# VisualightMicroBulb_03.net
KiCad netlist of a schematic drawn in EAGLE
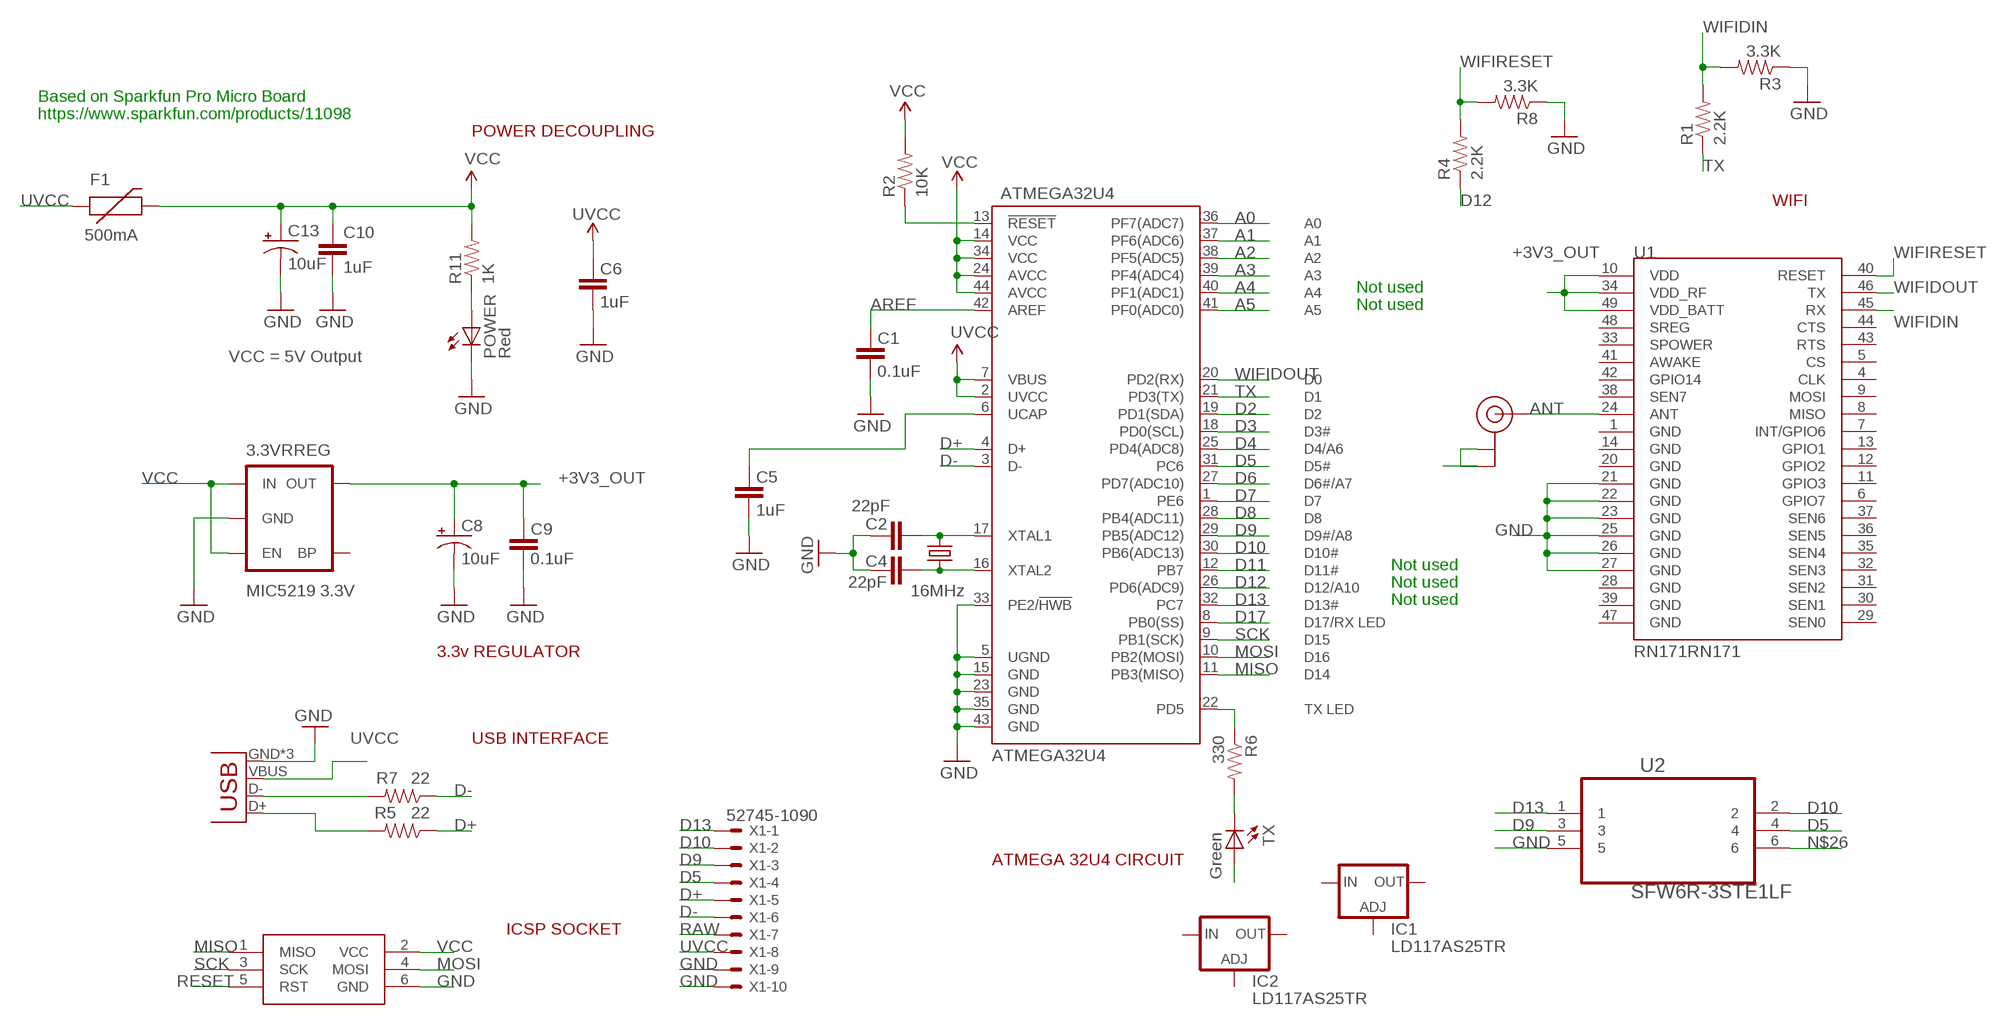
[diagram p0: schematic, sheet 1]

(export (version "E")
  (design (tool "Eeschema 10.0.6"))
  (components
    (comp (ref "3.3VRREG")
      (value "MIC5219 3.3V")
      (footprint "eagle-import:SOT23-5")
      (libsource (lib "eagle-import") (part "V_REG_MIC52193.3V"))
    )
    (comp (ref "ATMEGA32U4")
      (value "ATMEGA32U4")
      (footprint "eagle-import:SPARKFUN-DIGITALIC_TQFP44")
      (libsource (lib "eagle-import") (part "ATMEGA32U4TQFP"))
    )
    (comp (ref "C1")
      (value "0.1uF")
      (footprint "eagle-import:0402-CAP")
      (libsource (lib "eagle-import") (part "CAP0402-CAP"))
    )
    (comp (ref "C2")
      (value "22pF")
      (footprint "eagle-import:0402-CAP")
      (libsource (lib "eagle-import") (part "CAP0402-CAP"))
    )
    (comp (ref "C4")
      (value "22pF")
      (footprint "eagle-import:0402-CAP")
      (libsource (lib "eagle-import") (part "CAP0402-CAP"))
    )
    (comp (ref "C5")
      (value "1uF")
      (footprint "eagle-import:0402-CAP")
      (libsource (lib "eagle-import") (part "CAP0402-CAP"))
    )
    (comp (ref "C6")
      (value "1uF")
      (footprint "eagle-import:0402-CAP")
      (libsource (lib "eagle-import") (part "CAP0402-CAP"))
    )
    (comp (ref "C8")
      (value "10uF")
      (footprint "eagle-import:EIA3216")
      (libsource (lib "eagle-import") (part "CAP_POL1206"))
    )
    (comp (ref "C9")
      (value "0.1uF")
      (footprint "eagle-import:0402-CAP")
      (libsource (lib "eagle-import") (part "CAP0402-CAP"))
    )
    (comp (ref "C10")
      (value "1uF")
      (footprint "eagle-import:0402-CAP")
      (libsource (lib "eagle-import") (part "CAP0402-CAP"))
    )
    (comp (ref "C13")
      (value "10uF")
      (footprint "eagle-import:EIA3216")
      (libsource (lib "eagle-import") (part "CAP_POL1206"))
    )
    (comp (ref "F1")
      (value "500mA")
      (footprint "eagle-import:PTC-1206")
      (libsource (lib "eagle-import") (part "PTCSMD"))
    )
    (comp (ref "IC1")
      (value "LD117AS25TR")
      (footprint "eagle-import:SOT223")
      (libsource (lib "eagle-import") (part "LD117A?S25TR"))
    )
    (comp (ref "IC2")
      (value "LD117AS25TR")
      (footprint "eagle-import:SOT223")
      (libsource (lib "eagle-import") (part "LD117A?S25TR"))
    )
    (comp (ref "ISP1")
      (value "AVRISP-6")
      (footprint "eagle-import:AVRISP")
      (libsource (lib "eagle-import") (part "AVRISP-6"))
    )
    (comp (ref "POWER")
      (value "Red")
      (footprint "eagle-import:LED-0603")
      (libsource (lib "eagle-import") (part "LED0603"))
    )
    (comp (ref "R1")
      (value "2.2K")
      (footprint "eagle-import:0402-RES")
      (libsource (lib "eagle-import") (part "RESISTOR0402-RES"))
    )
    (comp (ref "R2")
      (value "10K")
      (footprint "eagle-import:0402-RES")
      (libsource (lib "eagle-import") (part "RESISTOR0402-RES"))
    )
    (comp (ref "R3")
      (value "3.3K")
      (footprint "eagle-import:0402-RES")
      (libsource (lib "eagle-import") (part "RESISTOR0402-RES"))
    )
    (comp (ref "R4")
      (value "2.2K")
      (footprint "eagle-import:0402-RES")
      (libsource (lib "eagle-import") (part "RESISTOR0402-RES"))
    )
    (comp (ref "R5")
      (value "22")
      (footprint "eagle-import:0402-RES")
      (libsource (lib "eagle-import") (part "RESISTOR0402-RES"))
    )
    (comp (ref "R6")
      (value "330")
      (footprint "eagle-import:0402-RES")
      (libsource (lib "eagle-import") (part "RESISTOR0402-RES"))
    )
    (comp (ref "R7")
      (value "22")
      (footprint "eagle-import:0402-RES")
      (libsource (lib "eagle-import") (part "RESISTOR0402-RES"))
    )
    (comp (ref "R8")
      (value "3.3K")
      (footprint "eagle-import:0402-RES")
      (libsource (lib "eagle-import") (part "RESISTOR0402-RES"))
    )
    (comp (ref "R11")
      (value "1K")
      (footprint "eagle-import:0402-RES")
      (libsource (lib "eagle-import") (part "RESISTOR0402-RES"))
    )
    (comp (ref "TX")
      (value "Green")
      (footprint "eagle-import:LED-0603")
      (libsource (lib "eagle-import") (part "LED0603"))
    )
    (comp (ref "U$1")
      (value "U.FL")
      (footprint "eagle-import:U.FL")
      (libsource (lib "eagle-import") (part "U.FL"))
    )
    (comp (ref "U1")
      (value "RN171RN171")
      (footprint "eagle-import:RN171")
      (libsource (lib "eagle-import") (part "RN171RN171"))
    )
    (comp (ref "U2")
      (value "SFW6R-3STE1LF")
      (footprint "eagle-import:FCI_SFW6R-3STE1LF")
      (libsource (lib "eagle-import") (part "SFW6R-3STE1LF"))
    )
    (comp (ref "X1")
      (value "52745-1090")
      (footprint "eagle-import:52745-1090")
      (libsource (lib "eagle-import") (part "52745-1090"))
    )
    (comp (ref "X2")
      (value "USB-MICROB")
      (footprint "eagle-import:USB-MICROB")
      (libsource (lib "eagle-import") (part "USB-MICROB"))
    )
    (comp (ref "Y1")
      (value "16MHz")
      (footprint "eagle-import:CRYSTAL-SMD-5X3")
      (libsource (lib "eagle-import") (part "CRYSTAL5X3"))
    )
  )
  (nets
    (net (code "1") (name "/+3V3_OUT") (class "Default")
      (node (ref "3.3VRREG") (pin "5") (pinfunction "OUT_5") (pintype "passive"))
      (node (ref "C8") (pin "A") (pinfunction "+_A") (pintype "passive"))
      (node (ref "C9") (pin "2") (pinfunction "2_2") (pintype "passive"))
      (node (ref "U1") (pin "10") (pinfunction "VDD_10") (pintype "bidirectional"))
      (node (ref "U1") (pin "34") (pinfunction "VDD_RF_34") (pintype "bidirectional"))
      (node (ref "U1") (pin "49") (pinfunction "VDD_BATT_49") (pintype "bidirectional"))
    )
    (net (code "2") (name "/A0") (class "Default")
      (node (ref "ATMEGA32U4") (pin "36") (pinfunction "PF7(ADC7)_36") (pintype "bidirectional"))
    )
    (net (code "3") (name "/A1") (class "Default")
      (node (ref "ATMEGA32U4") (pin "37") (pinfunction "PF6(ADC6)_37") (pintype "bidirectional"))
    )
    (net (code "4") (name "/A2") (class "Default")
      (node (ref "ATMEGA32U4") (pin "38") (pinfunction "PF5(ADC5)_38") (pintype "bidirectional"))
    )
    (net (code "5") (name "/A3") (class "Default")
      (node (ref "ATMEGA32U4") (pin "39") (pinfunction "PF4(ADC4)_39") (pintype "bidirectional"))
    )
    (net (code "6") (name "/A4") (class "Default")
      (node (ref "ATMEGA32U4") (pin "40") (pinfunction "PF1(ADC1)_40") (pintype "bidirectional"))
    )
    (net (code "7") (name "/A5") (class "Default")
      (node (ref "ATMEGA32U4") (pin "41") (pinfunction "PF0(ADC0)_41") (pintype "bidirectional"))
    )
    (net (code "8") (name "/ANT") (class "Default")
      (node (ref "U$1") (pin "P$3") (pinfunction "SIGNAL_P$3") (pintype "bidirectional"))
      (node (ref "U1") (pin "24") (pinfunction "ANT_24") (pintype "bidirectional"))
    )
    (net (code "9") (name "/AREF") (class "Default")
      (node (ref "ATMEGA32U4") (pin "42") (pinfunction "AREF_42") (pintype "bidirectional"))
      (node (ref "C1") (pin "2") (pinfunction "2_2") (pintype "passive"))
    )
    (net (code "10") (name "/D+") (class "Default")
      (node (ref "ATMEGA32U4") (pin "4") (pinfunction "D+_4") (pintype "bidirectional"))
      (node (ref "R5") (pin "1") (pinfunction "1_1") (pintype "passive"))
      (node (ref "X1") (pin "5") (pinfunction "S_5") (pintype "passive"))
    )
    (net (code "11") (name "/D-") (class "Default")
      (node (ref "ATMEGA32U4") (pin "3") (pinfunction "D-_3") (pintype "bidirectional"))
      (node (ref "R7") (pin "1") (pinfunction "1_1") (pintype "passive"))
      (node (ref "X1") (pin "6") (pinfunction "S_6") (pintype "passive"))
    )
    (net (code "12") (name "/D2") (class "Default")
      (node (ref "ATMEGA32U4") (pin "19") (pinfunction "PD1(SDA)_19") (pintype "bidirectional"))
    )
    (net (code "13") (name "/D3") (class "Default")
      (node (ref "ATMEGA32U4") (pin "18") (pinfunction "PD0(SCL)_18") (pintype "bidirectional"))
    )
    (net (code "14") (name "/D4") (class "Default")
      (node (ref "ATMEGA32U4") (pin "25") (pinfunction "PD4(ADC8)_25") (pintype "bidirectional"))
    )
    (net (code "15") (name "/D5") (class "Default")
      (node (ref "ATMEGA32U4") (pin "31") (pinfunction "PC6_31") (pintype "bidirectional"))
      (node (ref "U2") (pin "4") (pinfunction "4_4") (pintype "passive"))
      (node (ref "X1") (pin "4") (pinfunction "S_4") (pintype "passive"))
    )
    (net (code "16") (name "/D6") (class "Default")
      (node (ref "ATMEGA32U4") (pin "27") (pinfunction "PD7(ADC10)_27") (pintype "bidirectional"))
    )
    (net (code "17") (name "/D7") (class "Default")
      (node (ref "ATMEGA32U4") (pin "1") (pinfunction "PE6_1") (pintype "bidirectional"))
    )
    (net (code "18") (name "/D8") (class "Default")
      (node (ref "ATMEGA32U4") (pin "28") (pinfunction "PB4(ADC11)_28") (pintype "bidirectional"))
    )
    (net (code "19") (name "/D9") (class "Default")
      (node (ref "ATMEGA32U4") (pin "29") (pinfunction "PB5(ADC12)_29") (pintype "bidirectional"))
      (node (ref "U2") (pin "3") (pinfunction "3_3") (pintype "passive"))
      (node (ref "X1") (pin "3") (pinfunction "S_3") (pintype "passive"))
    )
    (net (code "20") (name "/D10") (class "Default")
      (node (ref "ATMEGA32U4") (pin "30") (pinfunction "PB6(ADC13)_30") (pintype "bidirectional"))
      (node (ref "U2") (pin "2") (pinfunction "2_2") (pintype "passive"))
      (node (ref "X1") (pin "2") (pinfunction "S_2") (pintype "passive"))
    )
    (net (code "21") (name "/D11") (class "Default")
      (node (ref "ATMEGA32U4") (pin "12") (pinfunction "PB7_12") (pintype "bidirectional"))
    )
    (net (code "22") (name "/D12") (class "Default")
      (node (ref "ATMEGA32U4") (pin "26") (pinfunction "PD6(ADC9)_26") (pintype "bidirectional"))
      (node (ref "R4") (pin "1") (pinfunction "1_1") (pintype "passive"))
    )
    (net (code "23") (name "/D13") (class "Default")
      (node (ref "ATMEGA32U4") (pin "32") (pinfunction "PC7_32") (pintype "bidirectional"))
      (node (ref "U2") (pin "1") (pinfunction "1_1") (pintype "passive"))
      (node (ref "X1") (pin "1") (pinfunction "S_1") (pintype "passive"))
    )
    (net (code "24") (name "/D17") (class "Default")
      (node (ref "ATMEGA32U4") (pin "8") (pinfunction "PB0(SS)_8") (pintype "bidirectional"))
    )
    (net (code "25") (name "/MISO") (class "Default")
      (node (ref "ATMEGA32U4") (pin "11") (pinfunction "PB3(MISO)_11") (pintype "bidirectional"))
      (node (ref "ISP1") (pin "1") (pinfunction "MISO_1") (pintype "input"))
    )
    (net (code "26") (name "/MOSI") (class "Default")
      (node (ref "ATMEGA32U4") (pin "10") (pinfunction "PB2(MOSI)_10") (pintype "bidirectional"))
      (node (ref "ISP1") (pin "4") (pinfunction "MOSI_4") (pintype "output"))
    )
    (net (code "27") (name "/N$26") (class "Default")
      (node (ref "U2") (pin "6") (pinfunction "6_6") (pintype "passive"))
    )
    (net (code "28") (name "/RAW") (class "Default")
      (node (ref "X1") (pin "7") (pinfunction "S_7") (pintype "passive"))
    )
    (net (code "29") (name "/RESET") (class "Default")
      (node (ref "ATMEGA32U4") (pin "13") (pinfunction "~{RESET}_13") (pintype "bidirectional"))
      (node (ref "ISP1") (pin "5") (pinfunction "RST_5") (pintype "output"))
      (node (ref "R2") (pin "1") (pinfunction "1_1") (pintype "passive"))
    )
    (net (code "30") (name "/SCK") (class "Default")
      (node (ref "ATMEGA32U4") (pin "9") (pinfunction "PB1(SCK)_9") (pintype "bidirectional"))
      (node (ref "ISP1") (pin "3") (pinfunction "SCK_3") (pintype "output"))
    )
    (net (code "31") (name "/TX") (class "Default")
      (node (ref "ATMEGA32U4") (pin "21") (pinfunction "PD3(TX)_21") (pintype "bidirectional"))
      (node (ref "R1") (pin "1") (pinfunction "1_1") (pintype "passive"))
    )
    (net (code "32") (name "/WIFIDIN") (class "Default")
      (node (ref "R1") (pin "2") (pinfunction "2_2") (pintype "passive"))
      (node (ref "R3") (pin "2") (pinfunction "2_2") (pintype "passive"))
      (node (ref "U1") (pin "45") (pinfunction "RX_45") (pintype "bidirectional"))
    )
    (net (code "33") (name "/WIFIDOUT") (class "Default")
      (node (ref "ATMEGA32U4") (pin "20") (pinfunction "PD2(RX)_20") (pintype "bidirectional"))
      (node (ref "U1") (pin "46") (pinfunction "TX_46") (pintype "bidirectional"))
    )
    (net (code "34") (name "/WIFIRESET") (class "Default")
      (node (ref "R4") (pin "2") (pinfunction "2_2") (pintype "passive"))
      (node (ref "R8") (pin "2") (pinfunction "2_2") (pintype "passive"))
      (node (ref "U1") (pin "40") (pinfunction "RESET_40") (pintype "bidirectional"))
    )
    (net (code "35") (name "GND") (class "Default")
      (node (ref "3.3VRREG") (pin "2") (pinfunction "GND_2") (pintype "input"))
      (node (ref "ATMEGA32U4") (pin "15") (pinfunction "GND_15") (pintype "bidirectional"))
      (node (ref "ATMEGA32U4") (pin "23") (pinfunction "GND_23") (pintype "bidirectional"))
      (node (ref "ATMEGA32U4") (pin "33") (pinfunction "PE2/~{HWB}_33") (pintype "bidirectional"))
      (node (ref "ATMEGA32U4") (pin "35") (pinfunction "GND_35") (pintype "bidirectional"))
      (node (ref "ATMEGA32U4") (pin "43") (pinfunction "GND_43") (pintype "bidirectional"))
      (node (ref "ATMEGA32U4") (pin "5") (pinfunction "UGND_5") (pintype "bidirectional"))
      (node (ref "C1") (pin "1") (pinfunction "1_1") (pintype "passive"))
      (node (ref "C10") (pin "2") (pinfunction "2_2") (pintype "passive"))
      (node (ref "C13") (pin "C") (pinfunction "-_C") (pintype "passive"))
      (node (ref "C2") (pin "2") (pinfunction "2_2") (pintype "passive"))
      (node (ref "C4") (pin "2") (pinfunction "2_2") (pintype "passive"))
      (node (ref "C5") (pin "1") (pinfunction "1_1") (pintype "passive"))
      (node (ref "C6") (pin "1") (pinfunction "1_1") (pintype "passive"))
      (node (ref "C8") (pin "C") (pinfunction "-_C") (pintype "passive"))
      (node (ref "C9") (pin "1") (pinfunction "1_1") (pintype "passive"))
      (node (ref "ISP1") (pin "6") (pinfunction "GND_6") (pintype "power_in"))
      (node (ref "POWER") (pin "C") (pinfunction "C_C") (pintype "passive"))
      (node (ref "R3") (pin "1") (pinfunction "1_1") (pintype "passive"))
      (node (ref "R8") (pin "1") (pinfunction "1_1") (pintype "passive"))
      (node (ref "U$1") (pin "P$1") (pinfunction "GND_P$1") (pintype "bidirectional"))
      (node (ref "U$1") (pin "P$2") (pinfunction "GND_P$2") (pintype "bidirectional"))
      (node (ref "U1") (pin "21") (pinfunction "GND_21") (pintype "bidirectional"))
      (node (ref "U1") (pin "22") (pinfunction "GND_22") (pintype "bidirectional"))
      (node (ref "U1") (pin "23") (pinfunction "GND_23") (pintype "bidirectional"))
      (node (ref "U1") (pin "25") (pinfunction "GND_25") (pintype "bidirectional"))
      (node (ref "U1") (pin "26") (pinfunction "GND_26") (pintype "bidirectional"))
      (node (ref "U1") (pin "27") (pinfunction "GND_27") (pintype "bidirectional"))
      (node (ref "U2") (pin "5") (pinfunction "5_5") (pintype "passive"))
      (node (ref "X1") (pin "10") (pinfunction "S_10") (pintype "passive"))
      (node (ref "X1") (pin "9") (pinfunction "S_9") (pintype "passive"))
      (node (ref "X2") (pin "GND") (pinfunction "GND_GND") (pintype "bidirectional"))
      (node (ref "X2") (pin "MT1") (pinfunction "GND_MT1") (pintype "bidirectional"))
      (node (ref "X2") (pin "MT2") (pinfunction "GND_MT2") (pintype "bidirectional"))
    )
    (net (code "36") (name "Net-(ATMEGA32U4-PD5)") (class "Default")
      (node (ref "ATMEGA32U4") (pin "22") (pinfunction "PD5_22") (pintype "bidirectional"))
      (node (ref "R6") (pin "1") (pinfunction "1_1") (pintype "passive"))
    )
    (net (code "37") (name "Net-(ATMEGA32U4-UCAP)") (class "Default")
      (node (ref "ATMEGA32U4") (pin "6") (pinfunction "UCAP_6") (pintype "bidirectional"))
      (node (ref "C5") (pin "2") (pinfunction "2_2") (pintype "passive"))
    )
    (net (code "38") (name "Net-(ATMEGA32U4-XTAL1)") (class "Default")
      (node (ref "ATMEGA32U4") (pin "17") (pinfunction "XTAL1_17") (pintype "bidirectional"))
      (node (ref "C2") (pin "1") (pinfunction "1_1") (pintype "passive"))
      (node (ref "Y1") (pin "3") (pinfunction "2_3") (pintype "passive"))
    )
    (net (code "39") (name "Net-(ATMEGA32U4-XTAL2)") (class "Default")
      (node (ref "ATMEGA32U4") (pin "16") (pinfunction "XTAL2_16") (pintype "bidirectional"))
      (node (ref "C4") (pin "1") (pinfunction "1_1") (pintype "passive"))
      (node (ref "Y1") (pin "1") (pinfunction "1_1") (pintype "passive"))
    )
    (net (code "40") (name "Net-(POWER-PadA)") (class "Default")
      (node (ref "POWER") (pin "A") (pinfunction "A_A") (pintype "passive"))
      (node (ref "R11") (pin "1") (pinfunction "1_1") (pintype "passive"))
    )
    (net (code "41") (name "Net-(R5-Pad2)") (class "Default")
      (node (ref "R5") (pin "2") (pinfunction "2_2") (pintype "passive"))
      (node (ref "X2") (pin "D+") (pinfunction "D+_D+") (pintype "bidirectional"))
    )
    (net (code "42") (name "Net-(R6-Pad2)") (class "Default")
      (node (ref "R6") (pin "2") (pinfunction "2_2") (pintype "passive"))
      (node (ref "TX") (pin "C") (pinfunction "C_C") (pintype "passive"))
    )
    (net (code "43") (name "Net-(R7-Pad2)") (class "Default")
      (node (ref "R7") (pin "2") (pinfunction "2_2") (pintype "passive"))
      (node (ref "X2") (pin "D-") (pinfunction "D-_D-") (pintype "bidirectional"))
    )
    (net (code "44") (name "UVCC") (class "Default")
      (node (ref "ATMEGA32U4") (pin "2") (pinfunction "UVCC_2") (pintype "bidirectional"))
      (node (ref "ATMEGA32U4") (pin "7") (pinfunction "VBUS_7") (pintype "bidirectional"))
      (node (ref "C6") (pin "2") (pinfunction "2_2") (pintype "passive"))
      (node (ref "F1") (pin "1") (pinfunction "1_1") (pintype "bidirectional"))
      (node (ref "X1") (pin "8") (pinfunction "S_8") (pintype "passive"))
      (node (ref "X2") (pin "VBUS") (pinfunction "VBUS_VBUS") (pintype "bidirectional"))
    )
    (net (code "45") (name "VCC") (class "Default")
      (node (ref "3.3VRREG") (pin "1") (pinfunction "IN_1") (pintype "input"))
      (node (ref "3.3VRREG") (pin "3") (pinfunction "EN_3") (pintype "input"))
      (node (ref "ATMEGA32U4") (pin "14") (pinfunction "VCC_14") (pintype "bidirectional"))
      (node (ref "ATMEGA32U4") (pin "24") (pinfunction "AVCC_24") (pintype "bidirectional"))
      (node (ref "ATMEGA32U4") (pin "34") (pinfunction "VCC_34") (pintype "bidirectional"))
      (node (ref "ATMEGA32U4") (pin "44") (pinfunction "AVCC_44") (pintype "bidirectional"))
      (node (ref "C10") (pin "1") (pinfunction "1_1") (pintype "passive"))
      (node (ref "C13") (pin "A") (pinfunction "+_A") (pintype "passive"))
      (node (ref "F1") (pin "2") (pinfunction "2_2") (pintype "bidirectional"))
      (node (ref "ISP1") (pin "2") (pinfunction "VCC_2") (pintype "power_in"))
      (node (ref "R11") (pin "2") (pinfunction "2_2") (pintype "passive"))
      (node (ref "R2") (pin "2") (pinfunction "2_2") (pintype "passive"))
      (node (ref "TX") (pin "A") (pinfunction "A_A") (pintype "passive"))
    )
    (net (code "46") (name "unconnected-(3.3VRREG-BP-Pad4)") (class "Default")
      (node (ref "3.3VRREG") (pin "4") (pinfunction "BP_4") (pintype "input"))
    )
    (net (code "47") (name "unconnected-(IC1-ADJ-Pad1)") (class "Default")
      (node (ref "IC1") (pin "1") (pinfunction "ADJ_1") (pintype "input"))
    )
    (net (code "48") (name "unconnected-(IC1-IN-Pad3)") (class "Default")
      (node (ref "IC1") (pin "3") (pinfunction "IN_3") (pintype "input"))
    )
    (net (code "49") (name "unconnected-(IC1-OUT-Pad4)") (class "Default")
      (node (ref "IC1") (pin "4") (pinfunction "OUT_4") (pintype "passive"))
    )
    (net (code "50") (name "unconnected-(IC2-ADJ-Pad1)") (class "Default")
      (node (ref "IC2") (pin "1") (pinfunction "ADJ_1") (pintype "input"))
    )
    (net (code "51") (name "unconnected-(IC2-IN-Pad3)") (class "Default")
      (node (ref "IC2") (pin "3") (pinfunction "IN_3") (pintype "input"))
    )
    (net (code "52") (name "unconnected-(IC2-OUT-Pad4)") (class "Default")
      (node (ref "IC2") (pin "4") (pinfunction "OUT_4") (pintype "passive"))
    )
    (net (code "53") (name "unconnected-(U1-AWAKE-Pad41)") (class "Default")
      (node (ref "U1") (pin "41") (pinfunction "AWAKE_41") (pintype "bidirectional"))
    )
    (net (code "54") (name "unconnected-(U1-CLK-Pad4)") (class "Default")
      (node (ref "U1") (pin "4") (pinfunction "CLK_4") (pintype "bidirectional"))
    )
    (net (code "55") (name "unconnected-(U1-CS-Pad5)") (class "Default")
      (node (ref "U1") (pin "5") (pinfunction "CS_5") (pintype "bidirectional"))
    )
    (net (code "56") (name "unconnected-(U1-CTS-Pad44)") (class "Default")
      (node (ref "U1") (pin "44") (pinfunction "CTS_44") (pintype "bidirectional"))
    )
    (net (code "57") (name "unconnected-(U1-GND-Pad1)") (class "Default")
      (node (ref "U1") (pin "1") (pinfunction "GND_1") (pintype "bidirectional"))
    )
    (net (code "58") (name "unconnected-(U1-GND-Pad14)") (class "Default")
      (node (ref "U1") (pin "14") (pinfunction "GND_14") (pintype "bidirectional"))
    )
    (net (code "59") (name "unconnected-(U1-GND-Pad20)") (class "Default")
      (node (ref "U1") (pin "20") (pinfunction "GND_20") (pintype "bidirectional"))
    )
    (net (code "60") (name "unconnected-(U1-GND-Pad28)") (class "Default")
      (node (ref "U1") (pin "28") (pinfunction "GND_28") (pintype "bidirectional"))
    )
    (net (code "61") (name "unconnected-(U1-GND-Pad39)") (class "Default")
      (node (ref "U1") (pin "39") (pinfunction "GND_39") (pintype "bidirectional"))
    )
    (net (code "62") (name "unconnected-(U1-GND-Pad47)") (class "Default")
      (node (ref "U1") (pin "47") (pinfunction "GND_47") (pintype "bidirectional"))
    )
    (net (code "63") (name "unconnected-(U1-GPIO1-Pad13)") (class "Default")
      (node (ref "U1") (pin "13") (pinfunction "GPIO1_13") (pintype "bidirectional"))
    )
    (net (code "64") (name "unconnected-(U1-GPIO2-Pad12)") (class "Default")
      (node (ref "U1") (pin "12") (pinfunction "GPIO2_12") (pintype "bidirectional"))
    )
    (net (code "65") (name "unconnected-(U1-GPIO3-Pad11)") (class "Default")
      (node (ref "U1") (pin "11") (pinfunction "GPIO3_11") (pintype "bidirectional"))
    )
    (net (code "66") (name "unconnected-(U1-GPIO7-Pad6)") (class "Default")
      (node (ref "U1") (pin "6") (pinfunction "GPIO7_6") (pintype "bidirectional"))
    )
    (net (code "67") (name "unconnected-(U1-GPIO14-Pad42)") (class "Default")
      (node (ref "U1") (pin "42") (pinfunction "GPIO14_42") (pintype "bidirectional"))
    )
    (net (code "68") (name "unconnected-(U1-INT{slash}GPIO6-Pad7)") (class "Default")
      (node (ref "U1") (pin "7") (pinfunction "INT/GPIO6_7") (pintype "bidirectional"))
    )
    (net (code "69") (name "unconnected-(U1-MISO-Pad8)") (class "Default")
      (node (ref "U1") (pin "8") (pinfunction "MISO_8") (pintype "bidirectional"))
    )
    (net (code "70") (name "unconnected-(U1-MOSI-Pad9)") (class "Default")
      (node (ref "U1") (pin "9") (pinfunction "MOSI_9") (pintype "bidirectional"))
    )
    (net (code "71") (name "unconnected-(U1-RTS-Pad43)") (class "Default")
      (node (ref "U1") (pin "43") (pinfunction "RTS_43") (pintype "bidirectional"))
    )
    (net (code "72") (name "unconnected-(U1-SEN0-Pad29)") (class "Default")
      (node (ref "U1") (pin "29") (pinfunction "SEN0_29") (pintype "bidirectional"))
    )
    (net (code "73") (name "unconnected-(U1-SEN1-Pad30)") (class "Default")
      (node (ref "U1") (pin "30") (pinfunction "SEN1_30") (pintype "bidirectional"))
    )
    (net (code "74") (name "unconnected-(U1-SEN2-Pad31)") (class "Default")
      (node (ref "U1") (pin "31") (pinfunction "SEN2_31") (pintype "bidirectional"))
    )
    (net (code "75") (name "unconnected-(U1-SEN3-Pad32)") (class "Default")
      (node (ref "U1") (pin "32") (pinfunction "SEN3_32") (pintype "bidirectional"))
    )
    (net (code "76") (name "unconnected-(U1-SEN4-Pad35)") (class "Default")
      (node (ref "U1") (pin "35") (pinfunction "SEN4_35") (pintype "bidirectional"))
    )
    (net (code "77") (name "unconnected-(U1-SEN5-Pad36)") (class "Default")
      (node (ref "U1") (pin "36") (pinfunction "SEN5_36") (pintype "bidirectional"))
    )
    (net (code "78") (name "unconnected-(U1-SEN6-Pad37)") (class "Default")
      (node (ref "U1") (pin "37") (pinfunction "SEN6_37") (pintype "bidirectional"))
    )
    (net (code "79") (name "unconnected-(U1-SEN7-Pad38)") (class "Default")
      (node (ref "U1") (pin "38") (pinfunction "SEN7_38") (pintype "bidirectional"))
    )
    (net (code "80") (name "unconnected-(U1-SPOWER-Pad33)") (class "Default")
      (node (ref "U1") (pin "33") (pinfunction "SPOWER_33") (pintype "bidirectional"))
    )
    (net (code "81") (name "unconnected-(U1-SREG-Pad48)") (class "Default")
      (node (ref "U1") (pin "48") (pinfunction "SREG_48") (pintype "bidirectional"))
    )
  )
)
